# apr_prj.net
KiCad netlist of a schematic drawn in Altium Designer
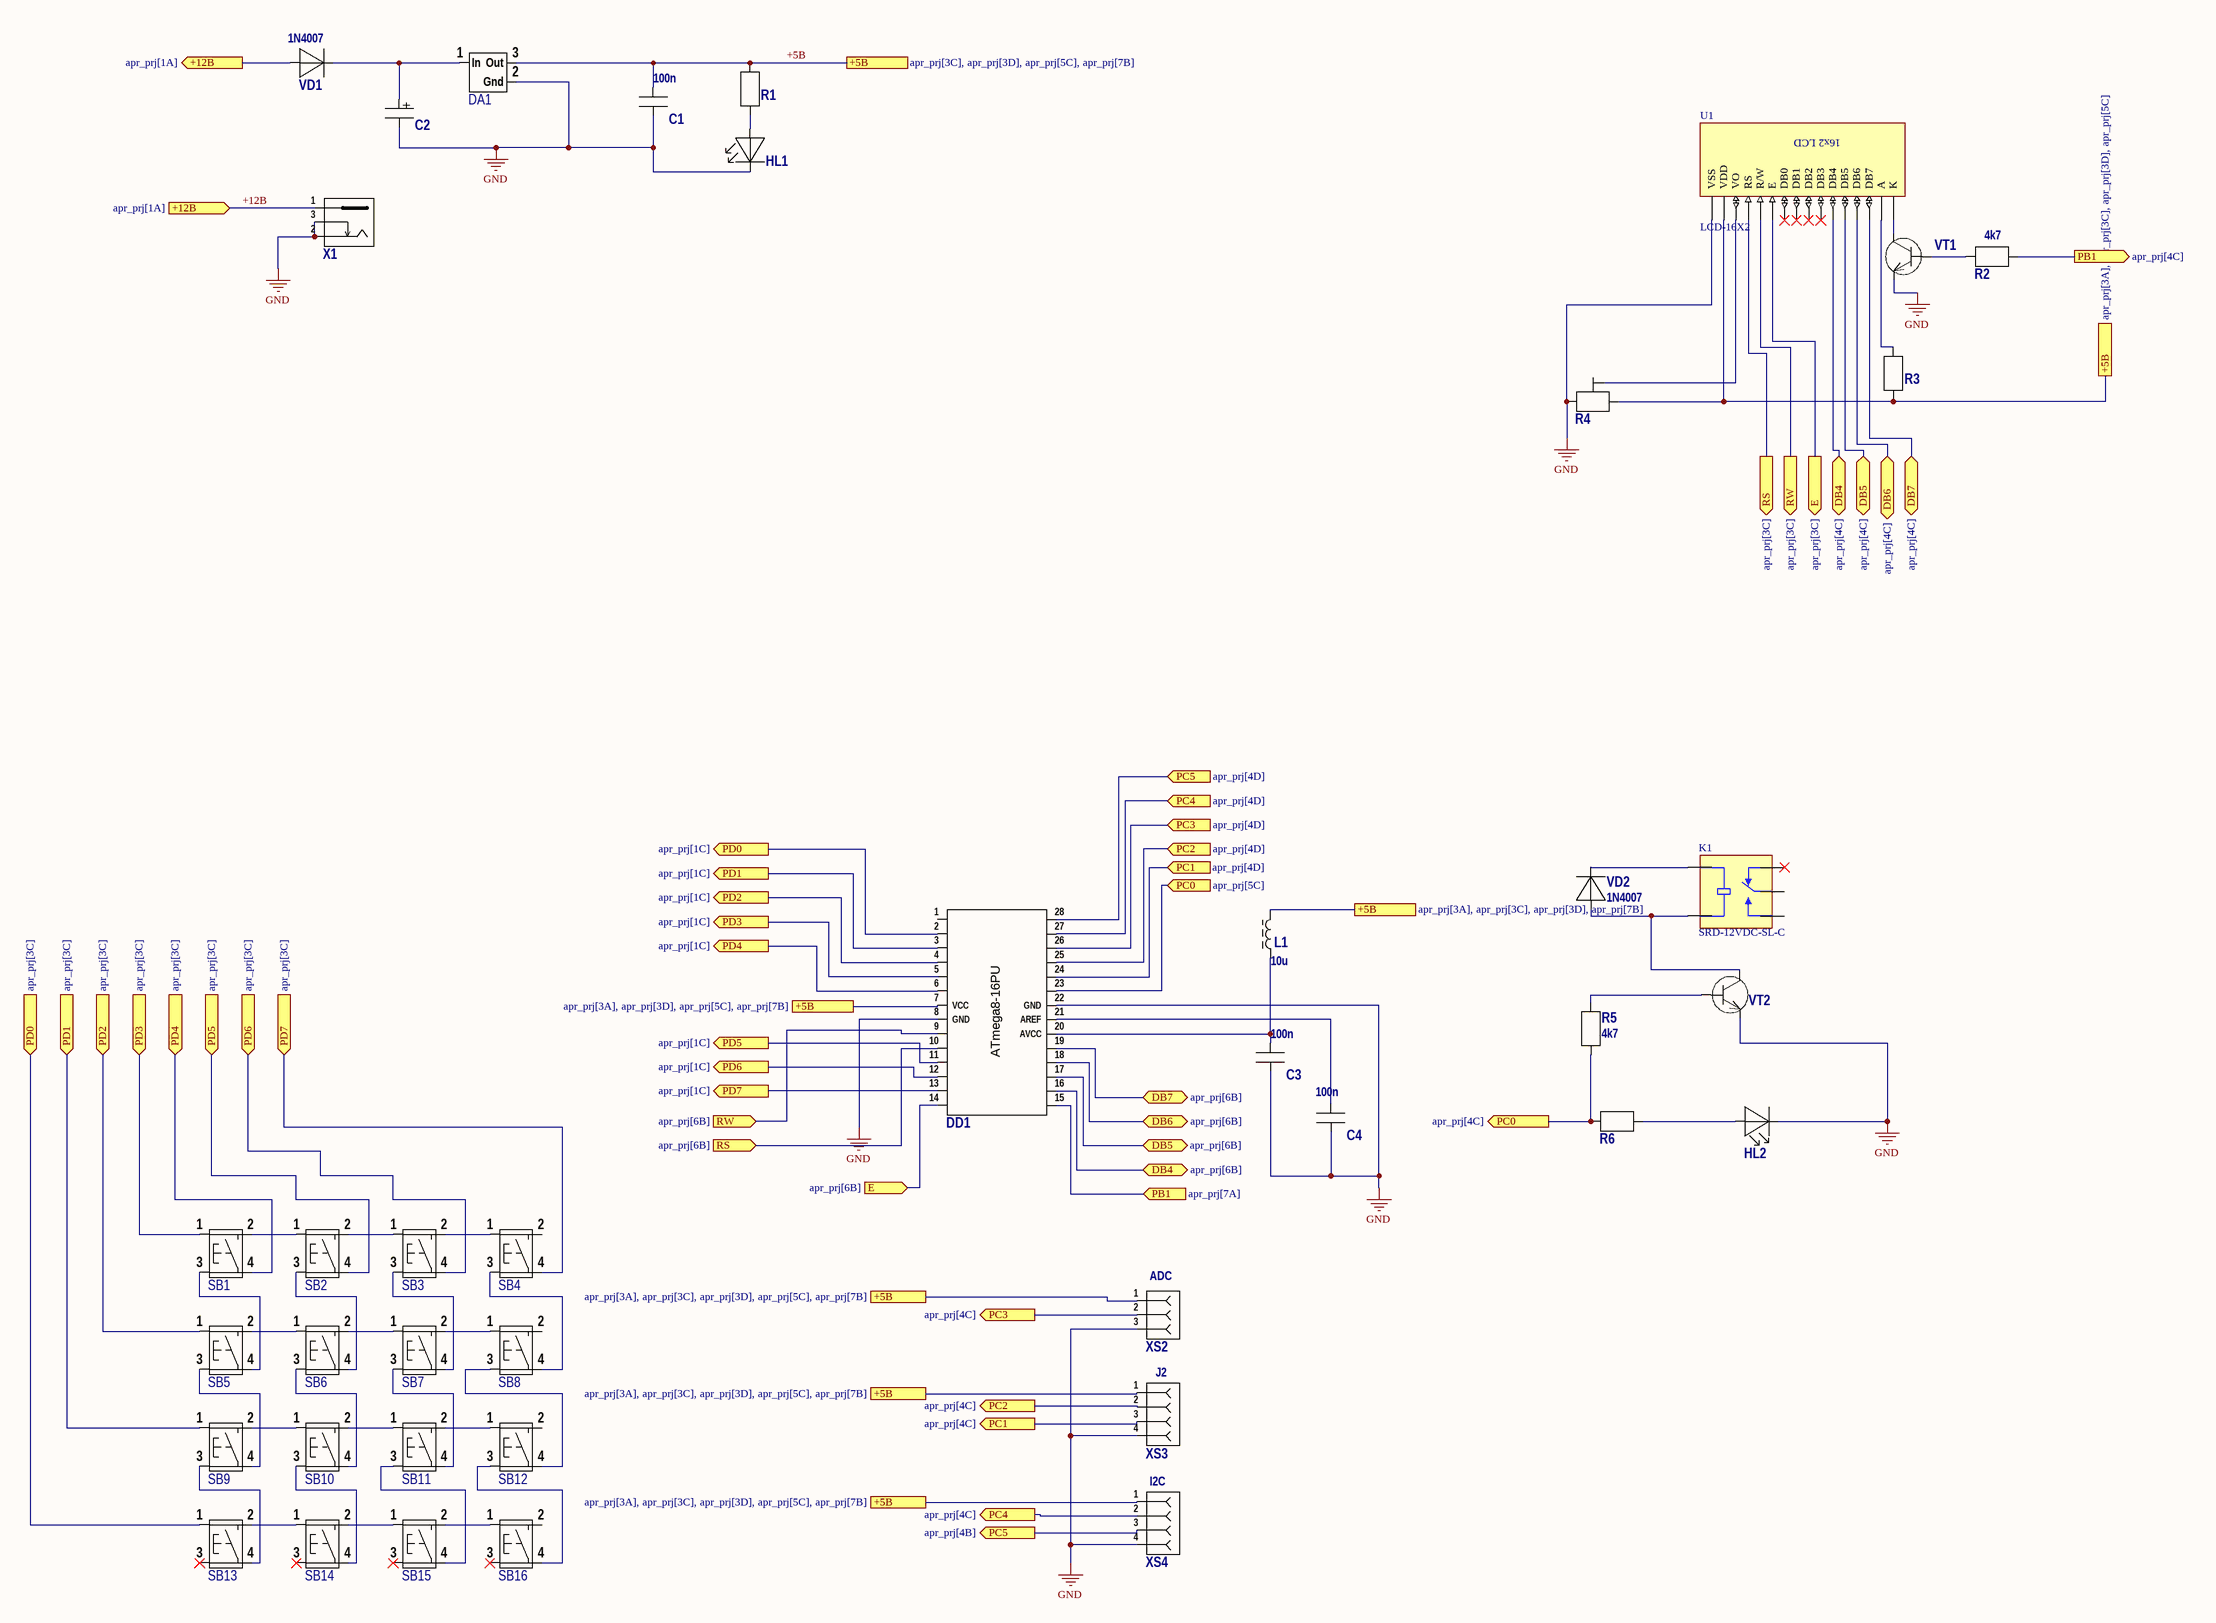
[diagram p0: apr_prj.SchDoc]

(export (version "E")
  (design (tool "Eeschema 10.0.6"))
  (components
    (comp (ref "C1")
      (value "100n")
      (footprint "CAP 0603 3D")
      (description "Конденсатор керамика")
      (libsource (lib "RLC V6.4_BVI") (part "C"))
    )
    (comp (ref "C2")
      (value "C Al R")
      (footprint "capr- 2.5D6.5H12")
      (description "Конденсатор алюминиевый радиальный")
      (libsource (lib "RLC V6.4_BVI") (part "C Al R"))
    )
    (comp (ref "C3")
      (value "100n")
      (footprint "CAP 0603 3D")
      (description "Конденсатор керамика")
      (libsource (lib "RLC V6.4_BVI") (part "C"))
    )
    (comp (ref "C4")
      (value "100n")
      (footprint "CAP 0603 3D")
      (description "Конденсатор керамика")
      (libsource (lib "RLC V6.4_BVI") (part "C"))
    )
    (comp (ref "DA1")
      (value "LM78xx")
      (footprint "TO-220_В")
      (description "Регулируемый стабилизатор напряжения     5…15V")
      (libsource (lib "DA V4.8_BVI") (part "LM78xx"))
    )
    (comp (ref "DD1")
      (value "ATmega8-16PU")
      (footprint "DIP-28  (300)")
      (description "Микроконтроллер 8-Бит   AVR   16МГц   8КБ Flash [DIP-28]")
      (libsource (lib "Microcontroller_V3.4_BVI") (part "ATmega8-16PU"))
    )
    (comp (ref "HL1")
      (value "fyls-0805???")
      (footprint "СД_SMD 2012_110")
      (description "Св. д. ЧИП 2012 (0805)")
      (libsource (lib "HL Светодиоды_V2.6 BVI") (part "fyls-0805...."))
    )
    (comp (ref "HL2")
      (value "fyls-0805???")
      (footprint "СД_SMD 2012_110")
      (description "Св. д. ЧИП 2012 (0805)")
      (libsource (lib "HL Светодиоды_V2.6 BVI") (part "fyls-0805...."))
    )
    (comp (ref "K1")
      (value "SRD-12VDC-SL-C")
      (footprint "RELAY_SRD-12VDC-SL-C")
      (description "General Purpose Non Latching 12VDC SPDT Through Hole Relays RoHS")
      (fields (field (name "MF") "Songle Relay"))
      (libsource (lib "SRD-12VDC-SL-C") (part "SRD-12VDC-SL-C"))
    )
    (comp (ref "L1")
      (value "10u")
      (footprint "B82422")
      (description "Индуктивность ЧИП (SMD)")
      (libsource (lib "RLC V6.4_BVI") (part "L x1"))
    )
    (comp (ref "R1")
      (value "R")
      (footprint "Res_0805 3D")
      (description "Резисторы плёночные (SMD; МЛТ; С2-33Н; MP9xxx)")
      (libsource (lib "RLC V6.4_BVI") (part "R"))
    )
    (comp (ref "R2")
      (value "4k7")
      (footprint "Res_0805 3D")
      (description "Резисторы плёночные (SMD; МЛТ; С2-33Н; MP9xxx)")
      (libsource (lib "RLC V6.4_BVI") (part "R"))
    )
    (comp (ref "R3")
      (value "R")
      (footprint "Res_0805 3D")
      (description "Резисторы плёночные (SMD; МЛТ; С2-33Н; MP9xxx)")
      (libsource (lib "RLC V6.4_BVI") (part "R"))
    )
    (comp (ref "R4")
      (value "R POT")
      (footprint "POT SH-655MCL")
      (description "Потенциометр BOURNS")
      (libsource (lib "RLC V6.4_BVI") (part "R POT"))
    )
    (comp (ref "R5")
      (value "4k7")
      (footprint "Res_0805 3D")
      (description "Резисторы плёночные (SMD; МЛТ; С2-33Н; MP9xxx)")
      (libsource (lib "RLC V6.4_BVI") (part "R"))
    )
    (comp (ref "R6")
      (value "R")
      (footprint "Res_0805 3D")
      (description "Резисторы плёночные (SMD; МЛТ; С2-33Н; MP9xxx)")
      (libsource (lib "RLC V6.4_BVI") (part "R"))
    )
    (comp (ref "SB1")
      (value "0670HIM")
      (footprint "250 _ 6,0-6,0-7,0")
      (description "Кнопка тактовая")
      (libsource (lib "Switches V3.4_BVI") (part "1_0670HIM"))
    )
    (comp (ref "SB2")
      (value "0670HIM")
      (footprint "250 _ 6,0-6,0-7,0")
      (description "Кнопка тактовая")
      (libsource (lib "Switches V3.4_BVI") (part "1_0670HIM"))
    )
    (comp (ref "SB3")
      (value "0670HIM")
      (footprint "250 _ 6,0-6,0-7,0")
      (description "Кнопка тактовая")
      (libsource (lib "Switches V3.4_BVI") (part "1_0670HIM"))
    )
    (comp (ref "SB4")
      (value "0670HIM")
      (footprint "250 _ 6,0-6,0-7,0")
      (description "Кнопка тактовая")
      (libsource (lib "Switches V3.4_BVI") (part "1_0670HIM"))
    )
    (comp (ref "SB5")
      (value "0670HIM")
      (footprint "250 _ 6,0-6,0-7,0")
      (description "Кнопка тактовая")
      (libsource (lib "Switches V3.4_BVI") (part "1_0670HIM"))
    )
    (comp (ref "SB6")
      (value "0670HIM")
      (footprint "250 _ 6,0-6,0-7,0")
      (description "Кнопка тактовая")
      (libsource (lib "Switches V3.4_BVI") (part "1_0670HIM"))
    )
    (comp (ref "SB7")
      (value "0670HIM")
      (footprint "250 _ 6,0-6,0-7,0")
      (description "Кнопка тактовая")
      (libsource (lib "Switches V3.4_BVI") (part "1_0670HIM"))
    )
    (comp (ref "SB8")
      (value "0670HIM")
      (footprint "250 _ 6,0-6,0-7,0")
      (description "Кнопка тактовая")
      (libsource (lib "Switches V3.4_BVI") (part "1_0670HIM"))
    )
    (comp (ref "SB9")
      (value "0670HIM")
      (footprint "250 _ 6,0-6,0-7,0")
      (description "Кнопка тактовая")
      (libsource (lib "Switches V3.4_BVI") (part "1_0670HIM"))
    )
    (comp (ref "SB10")
      (value "0670HIM")
      (footprint "250 _ 6,0-6,0-7,0")
      (description "Кнопка тактовая")
      (libsource (lib "Switches V3.4_BVI") (part "1_0670HIM"))
    )
    (comp (ref "SB11")
      (value "0670HIM")
      (footprint "250 _ 6,0-6,0-7,0")
      (description "Кнопка тактовая")
      (libsource (lib "Switches V3.4_BVI") (part "1_0670HIM"))
    )
    (comp (ref "SB12")
      (value "0670HIM")
      (footprint "250 _ 6,0-6,0-7,0")
      (description "Кнопка тактовая")
      (libsource (lib "Switches V3.4_BVI") (part "1_0670HIM"))
    )
    (comp (ref "SB13")
      (value "0670HIM")
      (footprint "250 _ 6,0-6,0-7,0")
      (description "Кнопка тактовая")
      (libsource (lib "Switches V3.4_BVI") (part "1_0670HIM"))
    )
    (comp (ref "SB14")
      (value "0670HIM")
      (footprint "250 _ 6,0-6,0-7,0")
      (description "Кнопка тактовая")
      (libsource (lib "Switches V3.4_BVI") (part "1_0670HIM"))
    )
    (comp (ref "SB15")
      (value "0670HIM")
      (footprint "250 _ 6,0-6,0-7,0")
      (description "Кнопка тактовая")
      (libsource (lib "Switches V3.4_BVI") (part "1_0670HIM"))
    )
    (comp (ref "SB16")
      (value "0670HIM")
      (footprint "250 _ 6,0-6,0-7,0")
      (description "Кнопка тактовая")
      (libsource (lib "Switches V3.4_BVI") (part "1_0670HIM"))
    )
    (comp (ref "U1")
      (value "LCD-16X2")
      (footprint "MODULE_LCD-16X2")
      (description "Display Development Tools 16x2 Black on Green Char LCD w Backlight")
      (fields (field (name "MF") "Gravitech"))
      (libsource (lib "LCD-16X2") (part "LCD-16X2"))
    )
    (comp (ref "VD1")
      (value "1N4007")
      (footprint "DO-41  (7.5)")
      (description "Диод  одиночный")
      (libsource (lib "VD_VT_V6.2 BVI") (part "Диод.  x1  (2)"))
    )
    (comp (ref "VD2")
      (value "1N4007")
      (footprint "DO-41  (7.5)")
      (description "Диод  одиночный")
      (libsource (lib "VD_VT_V6.2 BVI") (part "Диод.  x1  (2)"))
    )
    (comp (ref "VT1")
      (value "VT NPN")
      (footprint "КТ-26 КБЭ (2)")
      (description "Транзистор NPN")
      (libsource (lib "VD_VT_V6.2 BVI") (part "VT NPN"))
    )
    (comp (ref "VT2")
      (value "VT NPN")
      (footprint "КТ-26 КБЭ (2)")
      (description "Транзистор NPN")
      (libsource (lib "VD_VT_V6.2 BVI") (part "VT NPN"))
    )
    (comp (ref "X1")
      (value "Гнездо")
      (footprint "XKB_DC-005-5A-2.0")
      (description "Разъём питания")
      (libsource (lib "Connectors V8.3_BVI") (part "Гнездо с выкл."))
    )
    (comp (ref "XS2")
      (value "ADC")
      (footprint "DS1023-1*03")
      (description "Гнездо на плату 2.54мм 1х3 pin")
      (libsource (lib "Connectors V8.3_BVI") (part "Розет 1* 3  (2)"))
    )
    (comp (ref "XS3")
      (value "J2")
      (footprint "DS1023-1*04")
      (description "Гнездо на плату 2.54мм 1х4 pin")
      (libsource (lib "Connectors V8.3_BVI") (part "Розет 1* 4  (2)"))
    )
    (comp (ref "XS4")
      (value "I2C")
      (footprint "DS1023-1*04")
      (description "Гнездо на плату 2.54мм 1х4 pin")
      (libsource (lib "Connectors V8.3_BVI") (part "Розет 1* 4  (2)"))
    )
  )
  (nets
    (net (code "1") (name "/+5В") (class "Default")
      (node (ref "C1") (pin "1") (pintype "passive"))
      (node (ref "DA1") (pin "3") (pinfunction "Out_3") (pintype "passive"))
      (node (ref "DD1") (pin "7") (pinfunction "VCC_7") (pintype "passive"))
      (node (ref "L1") (pin "2") (pintype "passive"))
      (node (ref "R1") (pin "2") (pintype "passive"))
      (node (ref "R3") (pin "1") (pintype "passive"))
      (node (ref "R4") (pin "3") (pinfunction "3_3") (pintype "passive"))
      (node (ref "U1") (pin "2") (pinfunction "VDD_2") (pintype "power_in"))
      (node (ref "XS2") (pin "1") (pinfunction "1_1") (pintype "passive"))
      (node (ref "XS3") (pin "1") (pinfunction "1_1") (pintype "passive"))
      (node (ref "XS4") (pin "1") (pinfunction "1_1") (pintype "passive"))
    )
    (net (code "2") (name "/+12В") (class "Default")
      (node (ref "VD1") (pin "2") (pinfunction "A_2") (pintype "passive"))
      (node (ref "X1") (pin "1") (pinfunction "1_1") (pintype "passive"))
    )
    (net (code "3") (name "/DB4") (class "Default")
      (node (ref "DD1") (pin "16") (pinfunction "PB2_(SS/OC1B)_16") (pintype "passive"))
      (node (ref "U1") (pin "11") (pinfunction "DB4_11") (pintype "bidirectional"))
    )
    (net (code "4") (name "/DB5") (class "Default")
      (node (ref "DD1") (pin "17") (pinfunction "PB3_(MOSI/OC2)_17") (pintype "passive"))
      (node (ref "U1") (pin "12") (pinfunction "DB5_12") (pintype "bidirectional"))
    )
    (net (code "5") (name "/DB6") (class "Default")
      (node (ref "DD1") (pin "18") (pinfunction "PB4_(MISO)_18") (pintype "passive"))
      (node (ref "U1") (pin "13") (pinfunction "DB6_13") (pintype "bidirectional"))
    )
    (net (code "6") (name "/DB7") (class "Default")
      (node (ref "DD1") (pin "19") (pinfunction "PB5_(SCK)_19") (pintype "passive"))
      (node (ref "U1") (pin "14") (pinfunction "DB7_14") (pintype "bidirectional"))
    )
    (net (code "7") (name "/E") (class "Default")
      (node (ref "DD1") (pin "14") (pinfunction "(ICP1)_PB0_14") (pintype "passive"))
      (node (ref "U1") (pin "6") (pinfunction "E_6") (pintype "input"))
    )
    (net (code "8") (name "/PB1") (class "Default")
      (node (ref "DD1") (pin "15") (pinfunction "PB1_(OC1A)_15") (pintype "passive"))
      (node (ref "R2") (pin "1") (pintype "passive"))
    )
    (net (code "9") (name "/PC0") (class "Default")
      (node (ref "DD1") (pin "23") (pinfunction "PC0_(ADC0)_23") (pintype "passive"))
      (node (ref "R5") (pin "2") (pintype "passive"))
      (node (ref "R6") (pin "2") (pintype "passive"))
    )
    (net (code "10") (name "/PC1") (class "Default")
      (node (ref "DD1") (pin "24") (pinfunction "PC1_(ADC1)_24") (pintype "passive"))
      (node (ref "XS3") (pin "3") (pinfunction "3_3") (pintype "passive"))
    )
    (net (code "11") (name "/PC2") (class "Default")
      (node (ref "DD1") (pin "25") (pinfunction "PC2_(ADC2)_25") (pintype "passive"))
      (node (ref "XS3") (pin "2") (pinfunction "2_2") (pintype "passive"))
    )
    (net (code "12") (name "/PC3") (class "Default")
      (node (ref "DD1") (pin "26") (pinfunction "PC3_(ADC3)_26") (pintype "passive"))
      (node (ref "XS2") (pin "2") (pinfunction "2_2") (pintype "passive"))
    )
    (net (code "13") (name "/PC4") (class "Default")
      (node (ref "DD1") (pin "27") (pinfunction "PC4_(ADC4/SDA)_27") (pintype "passive"))
      (node (ref "XS4") (pin "2") (pinfunction "2_2") (pintype "passive"))
    )
    (net (code "14") (name "/PC5") (class "Default")
      (node (ref "DD1") (pin "28") (pinfunction "PC5_(ADC5/SCL)_28") (pintype "passive"))
      (node (ref "XS4") (pin "3") (pinfunction "3_3") (pintype "passive"))
    )
    (net (code "15") (name "/PD0") (class "Default")
      (node (ref "DD1") (pin "2") (pinfunction "(RXD)_PD0_2") (pintype "passive"))
      (node (ref "SB13") (pin "1") (pinfunction "1_1") (pintype "passive"))
    )
    (net (code "16") (name "/PD1") (class "Default")
      (node (ref "DD1") (pin "3") (pinfunction "(TXD)_PD1_3") (pintype "passive"))
      (node (ref "SB9") (pin "1") (pinfunction "1_1") (pintype "passive"))
    )
    (net (code "17") (name "/PD2") (class "Default")
      (node (ref "DD1") (pin "4") (pinfunction "(INT0)_PD2_4") (pintype "passive"))
      (node (ref "SB5") (pin "1") (pinfunction "1_1") (pintype "passive"))
    )
    (net (code "18") (name "/PD3") (class "Default")
      (node (ref "DD1") (pin "5") (pinfunction "(INT1)_PD3_5") (pintype "passive"))
      (node (ref "SB1") (pin "1") (pinfunction "1_1") (pintype "passive"))
    )
    (net (code "19") (name "/PD4") (class "Default")
      (node (ref "DD1") (pin "6") (pinfunction "(XCK/T0)_PD4_6") (pintype "passive"))
      (node (ref "SB1") (pin "4") (pinfunction "4_4") (pintype "passive"))
    )
    (net (code "20") (name "/PD5") (class "Default")
      (node (ref "DD1") (pin "11") (pinfunction "(T1)_PD5_11") (pintype "passive"))
      (node (ref "SB2") (pin "4") (pinfunction "4_4") (pintype "passive"))
    )
    (net (code "21") (name "/PD6") (class "Default")
      (node (ref "DD1") (pin "12") (pinfunction "(AIN0)_PD6_12") (pintype "passive"))
      (node (ref "SB3") (pin "4") (pinfunction "4_4") (pintype "passive"))
    )
    (net (code "22") (name "/PD7") (class "Default")
      (node (ref "DD1") (pin "13") (pinfunction "(AIN1)_PD7_13") (pintype "passive"))
      (node (ref "SB4") (pin "4") (pinfunction "4_4") (pintype "passive"))
    )
    (net (code "23") (name "/RS") (class "Default")
      (node (ref "DD1") (pin "10") (pinfunction "(XTAL2/TOSC2)_PB7_10") (pintype "passive"))
      (node (ref "U1") (pin "4") (pinfunction "RS_4") (pintype "input"))
    )
    (net (code "24") (name "/RW") (class "Default")
      (node (ref "DD1") (pin "9") (pinfunction "(XTAL1/TOSC1)_PB6_9") (pintype "passive"))
      (node (ref "U1") (pin "5") (pinfunction "R/W_5") (pintype "input"))
    )
    (net (code "25") (name "GND") (class "Default")
      (node (ref "C1") (pin "2") (pintype "passive"))
      (node (ref "C2") (pin "1") (pinfunction "-_1") (pintype "passive"))
      (node (ref "C3") (pin "2") (pintype "passive"))
      (node (ref "C4") (pin "2") (pintype "passive"))
      (node (ref "DA1") (pin "2") (pinfunction "Gnd_2") (pintype "passive"))
      (node (ref "DD1") (pin "22") (pinfunction "GND_22") (pintype "passive"))
      (node (ref "DD1") (pin "8") (pinfunction "GND_8") (pintype "passive"))
      (node (ref "HL1") (pin "1") (pinfunction "K_1") (pintype "passive"))
      (node (ref "HL2") (pin "1") (pinfunction "K_1") (pintype "passive"))
      (node (ref "R4") (pin "1") (pinfunction "1_1") (pintype "passive"))
      (node (ref "U1") (pin "1") (pinfunction "VSS_1") (pintype "power_in"))
      (node (ref "VT1") (pin "3") (pinfunction "E_3") (pintype "passive"))
      (node (ref "VT2") (pin "3") (pinfunction "E_3") (pintype "passive"))
      (node (ref "X1") (pin "2") (pinfunction "2_2") (pintype "passive"))
      (node (ref "X1") (pin "3") (pinfunction "3_3") (pintype "passive"))
      (node (ref "XS2") (pin "3") (pinfunction "3_3") (pintype "passive"))
      (node (ref "XS3") (pin "4") (pinfunction "4_4") (pintype "passive"))
      (node (ref "XS4") (pin "4") (pinfunction "4_4") (pintype "passive"))
    )
    (net (code "26") (name "Net-(C2-+)") (class "Default")
      (node (ref "C2") (pin "2") (pinfunction "+_2") (pintype "passive"))
      (node (ref "DA1") (pin "1") (pinfunction "In_1") (pintype "passive"))
      (node (ref "VD1") (pin "1") (pinfunction "K_1") (pintype "passive"))
    )
    (net (code "27") (name "Net-(DD1-AREF)") (class "Default")
      (node (ref "C4") (pin "1") (pintype "passive"))
      (node (ref "DD1") (pin "21") (pinfunction "AREF_21") (pintype "passive"))
    )
    (net (code "28") (name "Net-(DD1-AVCC)") (class "Default")
      (node (ref "C3") (pin "1") (pintype "passive"))
      (node (ref "DD1") (pin "20") (pinfunction "AVCC_20") (pintype "passive"))
      (node (ref "L1") (pin "1") (pintype "passive"))
    )
    (net (code "29") (name "Net-(HL1-A)") (class "Default")
      (node (ref "HL1") (pin "2") (pinfunction "A_2") (pintype "passive"))
      (node (ref "R1") (pin "1") (pintype "passive"))
    )
    (net (code "30") (name "Net-(HL2-A)") (class "Default")
      (node (ref "HL2") (pin "2") (pinfunction "A_2") (pintype "passive"))
      (node (ref "R6") (pin "1") (pintype "passive"))
    )
    (net (code "31") (name "Net-(SB1-Pad2)") (class "Default")
      (node (ref "SB1") (pin "2") (pinfunction "2_2") (pintype "passive"))
      (node (ref "SB2") (pin "1") (pinfunction "1_1") (pintype "passive"))
    )
    (net (code "32") (name "Net-(SB1-Pad3)") (class "Default")
      (node (ref "SB1") (pin "3") (pinfunction "3_3") (pintype "passive"))
      (node (ref "SB5") (pin "4") (pinfunction "4_4") (pintype "passive"))
    )
    (net (code "33") (name "Net-(SB2-Pad2)") (class "Default")
      (node (ref "SB2") (pin "2") (pinfunction "2_2") (pintype "passive"))
      (node (ref "SB3") (pin "1") (pinfunction "1_1") (pintype "passive"))
    )
    (net (code "34") (name "Net-(SB2-Pad3)") (class "Default")
      (node (ref "SB2") (pin "3") (pinfunction "3_3") (pintype "passive"))
      (node (ref "SB6") (pin "4") (pinfunction "4_4") (pintype "passive"))
    )
    (net (code "35") (name "Net-(SB3-Pad2)") (class "Default")
      (node (ref "SB3") (pin "2") (pinfunction "2_2") (pintype "passive"))
      (node (ref "SB4") (pin "1") (pinfunction "1_1") (pintype "passive"))
    )
    (net (code "36") (name "Net-(SB3-Pad3)") (class "Default")
      (node (ref "SB3") (pin "3") (pinfunction "3_3") (pintype "passive"))
      (node (ref "SB7") (pin "4") (pinfunction "4_4") (pintype "passive"))
    )
    (net (code "37") (name "Net-(SB4-Pad3)") (class "Default")
      (node (ref "SB4") (pin "3") (pinfunction "3_3") (pintype "passive"))
      (node (ref "SB8") (pin "4") (pinfunction "4_4") (pintype "passive"))
    )
    (net (code "38") (name "Net-(SB5-Pad2)") (class "Default")
      (node (ref "SB5") (pin "2") (pinfunction "2_2") (pintype "passive"))
      (node (ref "SB6") (pin "1") (pinfunction "1_1") (pintype "passive"))
    )
    (net (code "39") (name "Net-(SB5-Pad3)") (class "Default")
      (node (ref "SB5") (pin "3") (pinfunction "3_3") (pintype "passive"))
      (node (ref "SB9") (pin "4") (pinfunction "4_4") (pintype "passive"))
    )
    (net (code "40") (name "Net-(SB6-Pad2)") (class "Default")
      (node (ref "SB6") (pin "2") (pinfunction "2_2") (pintype "passive"))
      (node (ref "SB7") (pin "1") (pinfunction "1_1") (pintype "passive"))
    )
    (net (code "41") (name "Net-(SB7-Pad2)") (class "Default")
      (node (ref "SB7") (pin "2") (pinfunction "2_2") (pintype "passive"))
      (node (ref "SB8") (pin "1") (pinfunction "1_1") (pintype "passive"))
    )
    (net (code "42") (name "Net-(SB10-Pad1)") (class "Default")
      (node (ref "SB10") (pin "1") (pinfunction "1_1") (pintype "passive"))
      (node (ref "SB9") (pin "2") (pinfunction "2_2") (pintype "passive"))
    )
    (net (code "43") (name "Net-(SB10-Pad2)") (class "Default")
      (node (ref "SB10") (pin "2") (pinfunction "2_2") (pintype "passive"))
      (node (ref "SB11") (pin "1") (pinfunction "1_1") (pintype "passive"))
    )
    (net (code "44") (name "Net-(SB10-Pad3)") (class "Default")
      (node (ref "SB10") (pin "3") (pinfunction "3_3") (pintype "passive"))
      (node (ref "SB14") (pin "4") (pinfunction "4_4") (pintype "passive"))
    )
    (net (code "45") (name "Net-(SB10-Pad4)") (class "Default")
      (node (ref "SB10") (pin "4") (pinfunction "4_4") (pintype "passive"))
      (node (ref "SB6") (pin "3") (pinfunction "3_3") (pintype "passive"))
    )
    (net (code "46") (name "Net-(SB11-Pad2)") (class "Default")
      (node (ref "SB11") (pin "2") (pinfunction "2_2") (pintype "passive"))
      (node (ref "SB12") (pin "1") (pinfunction "1_1") (pintype "passive"))
    )
    (net (code "47") (name "Net-(SB11-Pad3)") (class "Default")
      (node (ref "SB11") (pin "3") (pinfunction "3_3") (pintype "passive"))
      (node (ref "SB15") (pin "4") (pinfunction "4_4") (pintype "passive"))
    )
    (net (code "48") (name "Net-(SB11-Pad4)") (class "Default")
      (node (ref "SB11") (pin "4") (pinfunction "4_4") (pintype "passive"))
      (node (ref "SB7") (pin "3") (pinfunction "3_3") (pintype "passive"))
    )
    (net (code "49") (name "Net-(SB12-Pad3)") (class "Default")
      (node (ref "SB12") (pin "3") (pinfunction "3_3") (pintype "passive"))
      (node (ref "SB16") (pin "4") (pinfunction "4_4") (pintype "passive"))
    )
    (net (code "50") (name "Net-(SB12-Pad4)") (class "Default")
      (node (ref "SB12") (pin "4") (pinfunction "4_4") (pintype "passive"))
      (node (ref "SB8") (pin "3") (pinfunction "3_3") (pintype "passive"))
    )
    (net (code "51") (name "Net-(SB13-Pad2)") (class "Default")
      (node (ref "SB13") (pin "2") (pinfunction "2_2") (pintype "passive"))
      (node (ref "SB14") (pin "1") (pinfunction "1_1") (pintype "passive"))
    )
    (net (code "52") (name "Net-(SB13-Pad4)") (class "Default")
      (node (ref "SB13") (pin "4") (pinfunction "4_4") (pintype "passive"))
      (node (ref "SB9") (pin "3") (pinfunction "3_3") (pintype "passive"))
    )
    (net (code "53") (name "Net-(SB14-Pad2)") (class "Default")
      (node (ref "SB14") (pin "2") (pinfunction "2_2") (pintype "passive"))
      (node (ref "SB15") (pin "1") (pinfunction "1_1") (pintype "passive"))
    )
    (net (code "54") (name "Net-(SB15-Pad2)") (class "Default")
      (node (ref "SB15") (pin "2") (pinfunction "2_2") (pintype "passive"))
      (node (ref "SB16") (pin "1") (pinfunction "1_1") (pintype "passive"))
    )
    (net (code "55") (name "Net-(U1-A)") (class "Default")
      (node (ref "R3") (pin "2") (pintype "passive"))
      (node (ref "U1") (pin "15") (pinfunction "A_15") (pintype "power_in"))
    )
    (net (code "56") (name "Net-(U1-K)") (class "Default")
      (node (ref "U1") (pin "16") (pinfunction "K_16") (pintype "power_in"))
      (node (ref "VT1") (pin "2") (pinfunction "C_2") (pintype "passive"))
    )
    (net (code "57") (name "Net-(U1-VO)") (class "Default")
      (node (ref "R4") (pin "2") (pinfunction "2_2") (pintype "passive"))
      (node (ref "U1") (pin "3") (pinfunction "VO_3") (pintype "bidirectional"))
    )
    (net (code "58") (name "Net-(VD2-A)") (class "Default")
      (node (ref "K1") (pin "COIL2") (pinfunction "COIL2_COIL2") (pintype "passive"))
      (node (ref "VD2") (pin "2") (pinfunction "A_2") (pintype "passive"))
      (node (ref "VT2") (pin "2") (pinfunction "C_2") (pintype "passive"))
    )
    (net (code "59") (name "Net-(VD2-K)") (class "Default")
      (node (ref "K1") (pin "COIL1") (pinfunction "COIL1_COIL1") (pintype "passive"))
      (node (ref "VD2") (pin "1") (pinfunction "K_1") (pintype "passive"))
    )
    (net (code "60") (name "Net-(VT1-B)") (class "Default")
      (node (ref "R2") (pin "2") (pintype "passive"))
      (node (ref "VT1") (pin "1") (pinfunction "B_1") (pintype "passive"))
    )
    (net (code "61") (name "Net-(VT2-B)") (class "Default")
      (node (ref "R5") (pin "1") (pintype "passive"))
      (node (ref "VT2") (pin "1") (pinfunction "B_1") (pintype "passive"))
    )
    (net (code "62") (name "unconnected-(DD1-(RESET)_PC6-Pad1)") (class "Default")
      (node (ref "DD1") (pin "1") (pinfunction "(RESET)_PC6_1") (pintype "passive"))
    )
    (net (code "63") (name "unconnected-(K1-PadCOM)") (class "Default")
      (node (ref "K1") (pin "COM") (pinfunction "COM_COM") (pintype "passive"))
    )
    (net (code "64") (name "unconnected-(K1-PadNC)") (class "Default")
      (node (ref "K1") (pin "NC") (pinfunction "NC_NC") (pintype "passive+no_connect"))
    )
    (net (code "65") (name "unconnected-(K1-PadNO)") (class "Default")
      (node (ref "K1") (pin "NO") (pinfunction "NO_NO") (pintype "passive"))
    )
    (net (code "66") (name "unconnected-(SB4-Pad2)") (class "Default")
      (node (ref "SB4") (pin "2") (pinfunction "2_2") (pintype "passive"))
    )
    (net (code "67") (name "unconnected-(SB8-Pad2)") (class "Default")
      (node (ref "SB8") (pin "2") (pinfunction "2_2") (pintype "passive"))
    )
    (net (code "68") (name "unconnected-(SB12-Pad2)") (class "Default")
      (node (ref "SB12") (pin "2") (pinfunction "2_2") (pintype "passive"))
    )
    (net (code "69") (name "unconnected-(SB13-Pad3)") (class "Default")
      (node (ref "SB13") (pin "3") (pinfunction "3_3") (pintype "passive+no_connect"))
    )
    (net (code "70") (name "unconnected-(SB14-Pad3)") (class "Default")
      (node (ref "SB14") (pin "3") (pinfunction "3_3") (pintype "passive+no_connect"))
    )
    (net (code "71") (name "unconnected-(SB15-Pad3)") (class "Default")
      (node (ref "SB15") (pin "3") (pinfunction "3_3") (pintype "passive+no_connect"))
    )
    (net (code "72") (name "unconnected-(SB16-Pad2)") (class "Default")
      (node (ref "SB16") (pin "2") (pinfunction "2_2") (pintype "passive"))
    )
    (net (code "73") (name "unconnected-(SB16-Pad3)") (class "Default")
      (node (ref "SB16") (pin "3") (pinfunction "3_3") (pintype "passive+no_connect"))
    )
    (net (code "74") (name "unconnected-(U1-DB0-Pad7)") (class "Default")
      (node (ref "U1") (pin "7") (pinfunction "DB0_7") (pintype "bidirectional+no_connect"))
    )
    (net (code "75") (name "unconnected-(U1-DB1-Pad8)") (class "Default")
      (node (ref "U1") (pin "8") (pinfunction "DB1_8") (pintype "bidirectional+no_connect"))
    )
    (net (code "76") (name "unconnected-(U1-DB2-Pad9)") (class "Default")
      (node (ref "U1") (pin "9") (pinfunction "DB2_9") (pintype "bidirectional+no_connect"))
    )
    (net (code "77") (name "unconnected-(U1-DB3-Pad10)") (class "Default")
      (node (ref "U1") (pin "10") (pinfunction "DB3_10") (pintype "bidirectional+no_connect"))
    )
  )
)
